# synth-zodiac-capricorn-vcf-mod.net
KiCad netlist of a schematic drawn in EAGLE
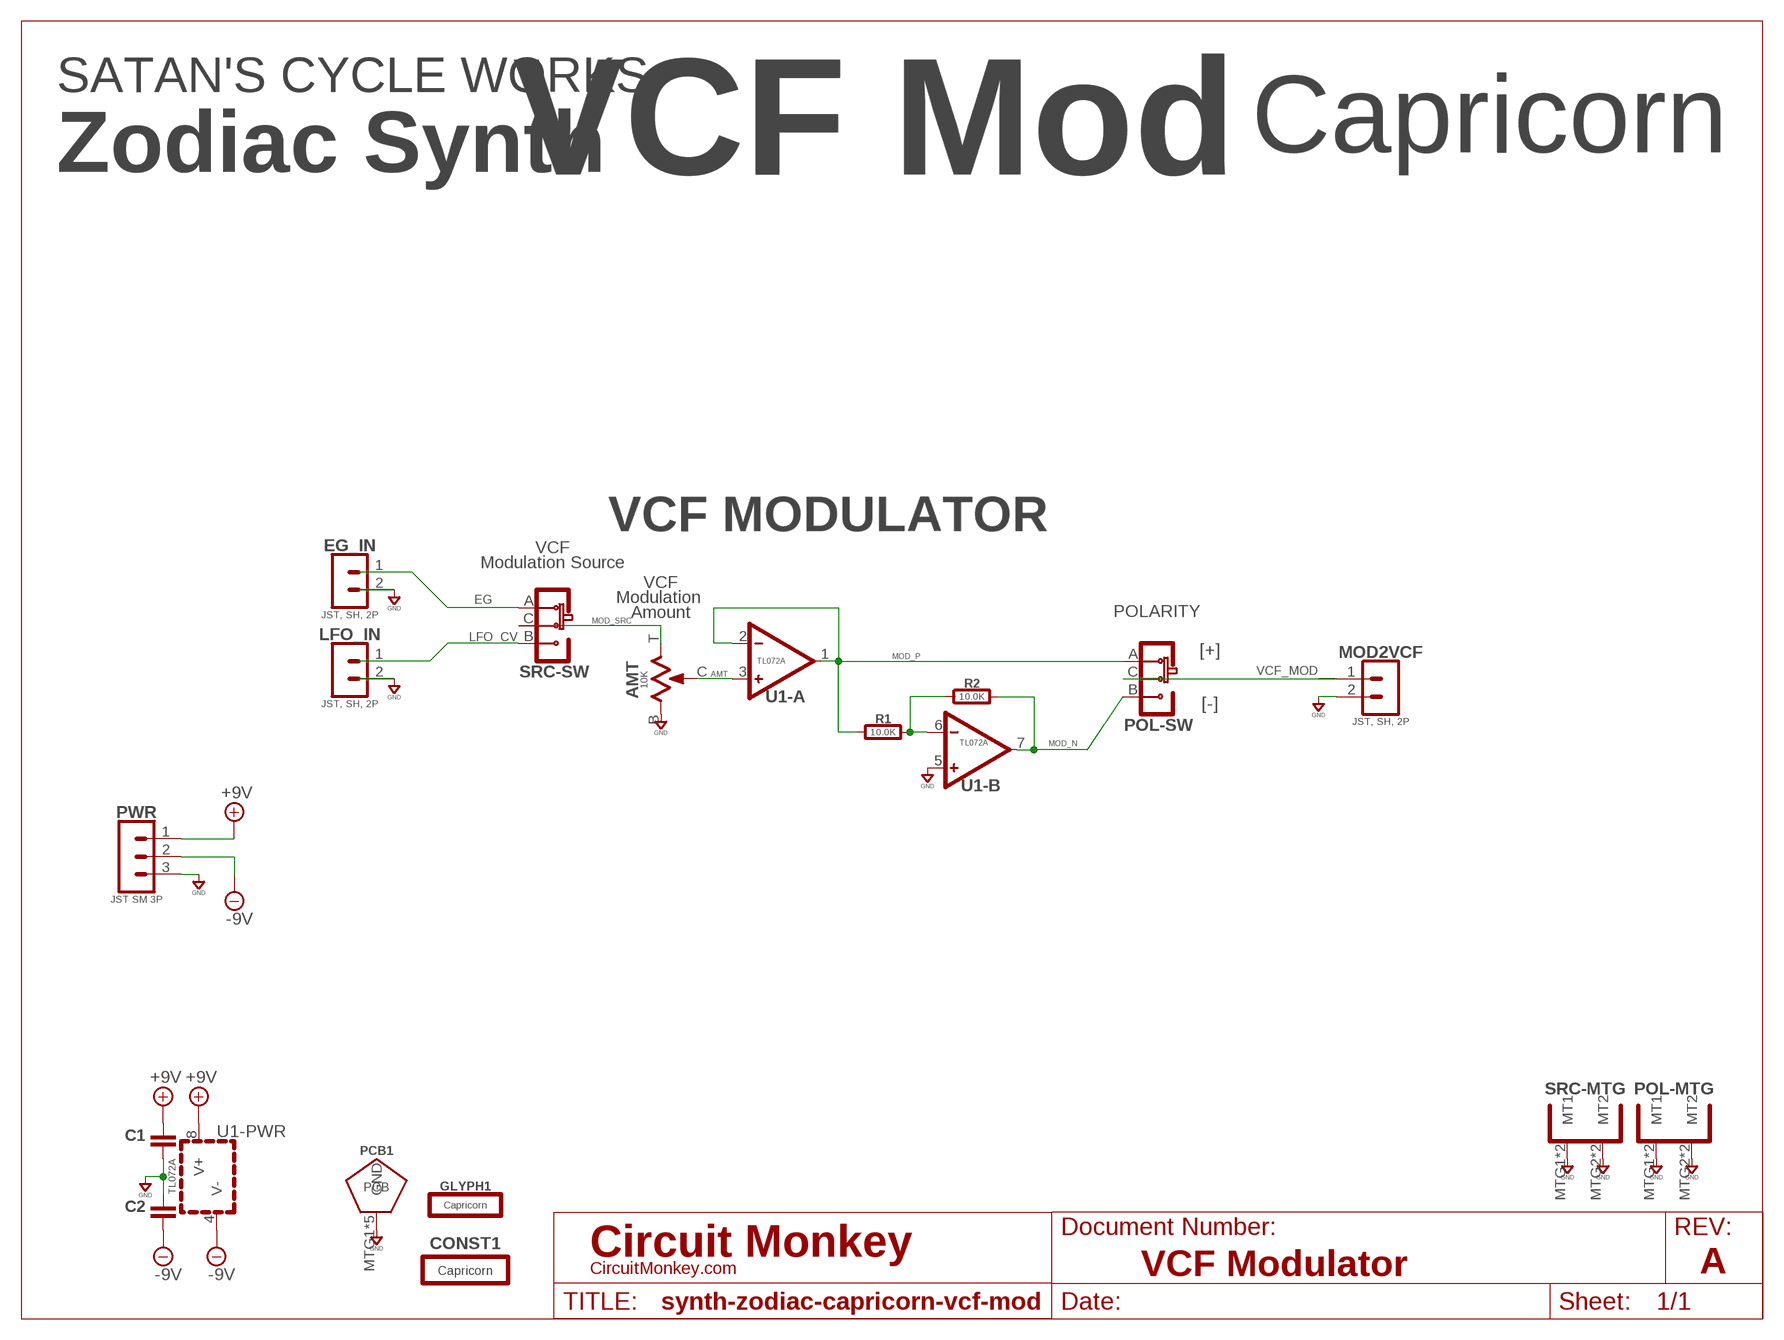
[diagram p0: schematic, sheet 1]

(export (version "E")
  (design (tool "Eeschema 10.0.6"))
  (components
    (comp (ref "AMT")
      (value "10K")
      (footprint "eagle-import:POT-RV9110")
      (fields (field (name "MFR") "Tayda") (field (name "MPN") "RV9110NO-OS15A00"))
      (libsource (lib "eagle-import") (part "TRIMPOT9MM_PCB_SHAFT"))
    )
    (comp (ref "C1")
      (value "0.1uF")
      (footprint "eagle-import:0603-CAP")
      (libsource (lib "eagle-import") (part "CAPACITOR0603"))
    )
    (comp (ref "C2")
      (value "0.1uF")
      (footprint "eagle-import:0603-CAP")
      (libsource (lib "eagle-import") (part "CAPACITOR0603"))
    )
    (comp (ref "CONST1")
      (value "Capricorn")
      (footprint "eagle-import:CAPRICORN-CONST")
      (libsource (lib "eagle-import") (part "CONSTELLATION-CAPRICORN"))
    )
    (comp (ref "EG_IN")
      (value "JST, SH, 2P")
      (footprint "eagle-import:BM02B-SRSS-TB")
      (fields (field (name "MFR") "JST") (field (name "MPN") "BMB02B-SRSS-TB"))
      (libsource (lib "eagle-import") (part "02P-SM-VT-SMT"))
    )
    (comp (ref "GLYPH1")
      (value "Capricorn")
      (footprint "eagle-import:CAPRICORN-GLYPH")
      (libsource (lib "eagle-import") (part "GLYPH-CAPRICORN"))
    )
    (comp (ref "LFO_IN")
      (value "JST, SH, 2P")
      (footprint "eagle-import:BM02B-SRSS-TB")
      (fields (field (name "MFR") "JST") (field (name "MPN") "BMB02B-SRSS-TB"))
      (libsource (lib "eagle-import") (part "02P-SM-VT-SMT"))
    )
    (comp (ref "MOD2VCF")
      (value "JST, SH, 2P")
      (footprint "eagle-import:BM02B-SRSS-TB")
      (fields (field (name "MFR") "JST") (field (name "MPN") "BMB02B-SRSS-TB"))
      (libsource (lib "eagle-import") (part "02P-SM-VT-SMT"))
    )
    (comp (ref "PCB1")
      (value "PCB FAB")
      (footprint "eagle-import:PENTAGON-40MM-RAD")
      (libsource (lib "eagle-import") (part "PENTAGON-40R"))
    )
    (comp (ref "POL")
      (value "SLIDE-SPDT-MNTSS-12-F45-TH-PCB-2")
      (footprint "eagle-import:SS-12-F45-PNL-SMT-2")
      (fields (field (name "MFR") "Tayda") (field (name "MPN") "A-659/A-5111/A-5104"))
      (libsource (lib "eagle-import") (part "SLIDE-SPDT-MNTSS-12-F45-TH-PCB-2"))
    )
    (comp (ref "PWR")
      (value "JST SM 3P")
      (footprint "eagle-import:BM03B-SRSS-TB")
      (fields (field (name "MFR") "JST") (field (name "MPN") "BM03B-SRSS-TB"))
      (libsource (lib "eagle-import") (part "03P-SM-VT-SMT"))
    )
    (comp (ref "R1")
      (value "10.0K")
      (footprint "eagle-import:0603-RES")
      (libsource (lib "eagle-import") (part "RESISTOR0603"))
    )
    (comp (ref "R2")
      (value "10.0K")
      (footprint "eagle-import:0603-RES")
      (libsource (lib "eagle-import") (part "RESISTOR0603"))
    )
    (comp (ref "SRC")
      (value "SLIDE-SPDT-MNTSS-12-F45-TH-PCB-2")
      (footprint "eagle-import:SS-12-F45-PNL-SMT-2")
      (fields (field (name "MFR") "Tayda") (field (name "MPN") "A-659/A-5111/A-5104"))
      (libsource (lib "eagle-import") (part "SLIDE-SPDT-MNTSS-12-F45-TH-PCB-2"))
    )
    (comp (ref "U1")
      (value "TL072A")
      (footprint "eagle-import:SOP08")
      (fields (field (name "MFR") "ST"))
      (libsource (lib "eagle-import") (part "DUALTL072A"))
    )
  )
  (nets
    (net (code "1") (name "+9V") (class "Default")
      (node (ref "C1") (pin "1") (pinfunction "1_1") (pintype "passive"))
      (node (ref "PWR") (pin "1") (pinfunction "1_1") (pintype "passive"))
      (node (ref "U1") (pin "8") (pinfunction "V+_8") (pintype "power_in"))
    )
    (net (code "2") (name "-9V") (class "Default")
      (node (ref "C2") (pin "2") (pinfunction "2_2") (pintype "passive"))
      (node (ref "PWR") (pin "2") (pinfunction "2_2") (pintype "passive"))
      (node (ref "U1") (pin "4") (pinfunction "V-_4") (pintype "power_in"))
    )
    (net (code "3") (name "/AMT") (class "Default")
      (node (ref "AMT") (pin "C") (pinfunction "2_C") (pintype "passive"))
      (node (ref "U1") (pin "3") (pinfunction "+_3") (pintype "input"))
    )
    (net (code "4") (name "/EG") (class "Default")
      (node (ref "EG_IN") (pin "1") (pinfunction "1_1") (pintype "passive"))
      (node (ref "SRC") (pin "A") (pinfunction "A_A") (pintype "bidirectional"))
    )
    (net (code "5") (name "/LFO_CV") (class "Default")
      (node (ref "LFO_IN") (pin "1") (pinfunction "1_1") (pintype "passive"))
      (node (ref "SRC") (pin "B") (pinfunction "B_B") (pintype "bidirectional"))
    )
    (net (code "6") (name "/MOD_N") (class "Default")
      (node (ref "POL") (pin "B") (pinfunction "B_B") (pintype "bidirectional"))
      (node (ref "R2") (pin "2") (pinfunction "2_2") (pintype "passive"))
      (node (ref "U1") (pin "7") (pinfunction "OUT_7") (pintype "output"))
    )
    (net (code "7") (name "/MOD_P") (class "Default")
      (node (ref "POL") (pin "A") (pinfunction "A_A") (pintype "bidirectional"))
      (node (ref "R1") (pin "1") (pinfunction "1_1") (pintype "passive"))
      (node (ref "U1") (pin "1") (pinfunction "OUT_1") (pintype "output"))
      (node (ref "U1") (pin "2") (pinfunction "-_2") (pintype "input"))
    )
    (net (code "8") (name "/MOD_SRC") (class "Default")
      (node (ref "AMT") (pin "T") (pinfunction "3_T") (pintype "passive"))
      (node (ref "SRC") (pin "C") (pinfunction "C_C") (pintype "bidirectional"))
    )
    (net (code "9") (name "/VCF_MOD") (class "Default")
      (node (ref "MOD2VCF") (pin "1") (pinfunction "1_1") (pintype "passive"))
      (node (ref "POL") (pin "C") (pinfunction "C_C") (pintype "bidirectional"))
    )
    (net (code "10") (name "GND") (class "Default")
      (node (ref "AMT") (pin "B") (pinfunction "1_B") (pintype "passive"))
      (node (ref "C1") (pin "2") (pinfunction "2_2") (pintype "passive"))
      (node (ref "C2") (pin "1") (pinfunction "1_1") (pintype "passive"))
      (node (ref "EG_IN") (pin "2") (pinfunction "2_2") (pintype "passive"))
      (node (ref "LFO_IN") (pin "2") (pinfunction "2_2") (pintype "passive"))
      (node (ref "MOD2VCF") (pin "2") (pinfunction "2_2") (pintype "passive"))
      (node (ref "PCB1") (pin "MTG1") (pinfunction "GND_MTG1") (pintype "bidirectional"))
      (node (ref "PCB1") (pin "MTG2") (pinfunction "GND_MTG2") (pintype "bidirectional"))
      (node (ref "PCB1") (pin "MTG3") (pinfunction "GND_MTG3") (pintype "bidirectional"))
      (node (ref "PCB1") (pin "MTG4") (pinfunction "GND_MTG4") (pintype "bidirectional"))
      (node (ref "PCB1") (pin "MTG5") (pinfunction "GND_MTG5") (pintype "bidirectional"))
      (node (ref "POL") (pin "MTG1") (pinfunction "MT1_MTG1") (pintype "bidirectional"))
      (node (ref "POL") (pin "MTG2") (pinfunction "MT2_MTG2") (pintype "bidirectional"))
      (node (ref "POL") (pin "MTG3") (pinfunction "MT1_MTG3") (pintype "bidirectional"))
      (node (ref "POL") (pin "MTG4") (pinfunction "MT2_MTG4") (pintype "bidirectional"))
      (node (ref "PWR") (pin "3") (pinfunction "3_3") (pintype "passive"))
      (node (ref "SRC") (pin "MTG1") (pinfunction "MT1_MTG1") (pintype "bidirectional"))
      (node (ref "SRC") (pin "MTG2") (pinfunction "MT2_MTG2") (pintype "bidirectional"))
      (node (ref "SRC") (pin "MTG3") (pinfunction "MT1_MTG3") (pintype "bidirectional"))
      (node (ref "SRC") (pin "MTG4") (pinfunction "MT2_MTG4") (pintype "bidirectional"))
      (node (ref "U1") (pin "5") (pinfunction "+_5") (pintype "input"))
    )
    (net (code "11") (name "Net-(U1B--)") (class "Default")
      (node (ref "R1") (pin "2") (pinfunction "2_2") (pintype "passive"))
      (node (ref "R2") (pin "1") (pinfunction "1_1") (pintype "passive"))
      (node (ref "U1") (pin "6") (pinfunction "-_6") (pintype "input"))
    )
  )
)
